# Reflow_Panel_Rev_D.net
KiCad netlist of a schematic drawn in EAGLE
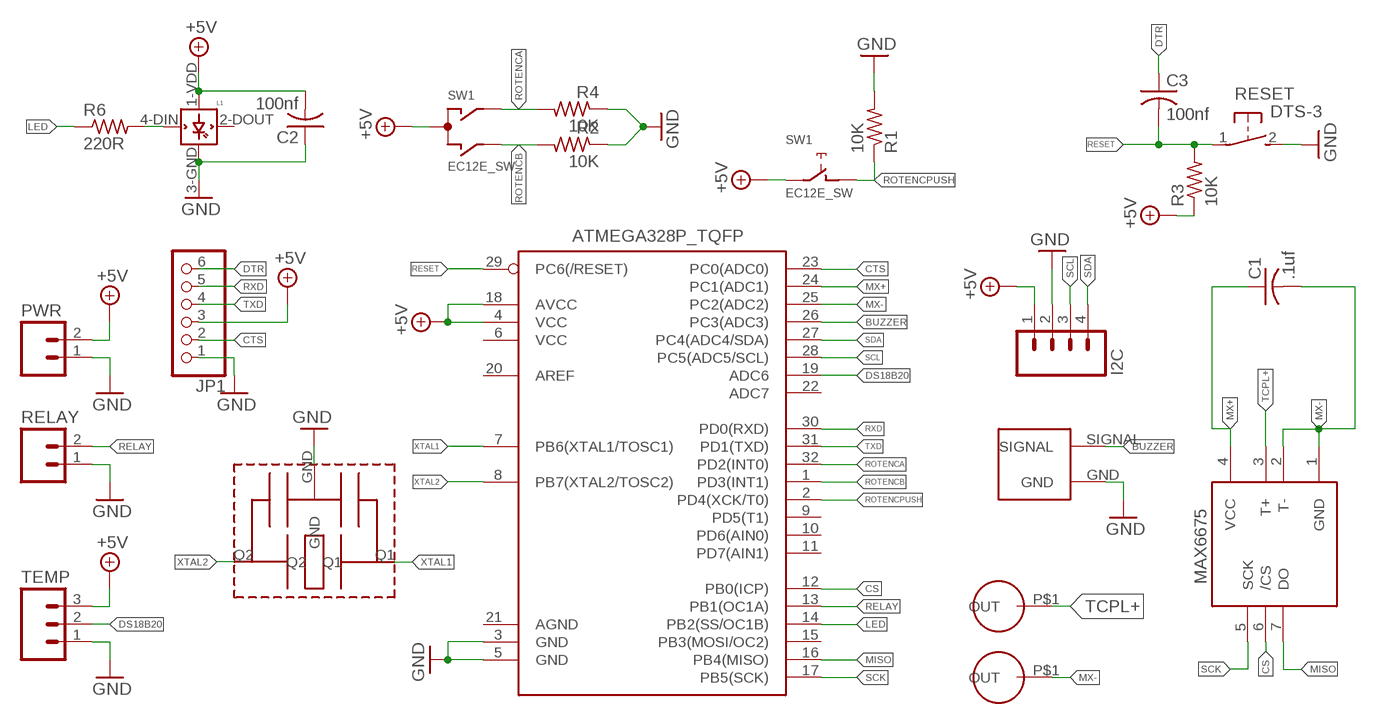
[diagram p0: schematic, sheet 1]

(export (version "E")
  (design (tool "Eeschema 10.0.6"))
  (components
    (comp (ref "C1")
      (value ".1uf")
      (footprint "eagle-import:C0805")
      (libsource (lib "eagle-import") (part "C-USC0805"))
    )
    (comp (ref "C2")
      (value "100nf")
      (footprint "eagle-import:C0805")
      (libsource (lib "eagle-import") (part "C-USC0805"))
    )
    (comp (ref "C3")
      (value "100nf")
      (footprint "eagle-import:C0805")
      (libsource (lib "eagle-import") (part "C-USC0805"))
    )
    (comp (ref "I2C")
      (value "M04LOCK_LONGPADS")
      (footprint "eagle-import:1X04_LOCK_LONGPADS")
      (libsource (lib "eagle-import") (part "M04LOCK_LONGPADS"))
    )
    (comp (ref "IC2")
      (value "MAX6675")
      (footprint "eagle-import:SO08")
      (libsource (lib "eagle-import") (part "MAX6675"))
    )
    (comp (ref "JP1")
      (value "PINHD-1X6LOCK")
      (footprint "eagle-import:1X06-BIGLOCK")
      (libsource (lib "eagle-import") (part "PINHD-1X6LOCK"))
    )
    (comp (ref "L1")
      (value "WS2812B_")
      (footprint "eagle-import:WS2812B")
      (libsource (lib "eagle-import") (part "WS2812B_"))
    )
    (comp (ref "PWR")
      (value "M02LOCK")
      (footprint "eagle-import:1X02_LOCK")
      (libsource (lib "eagle-import") (part "M02LOCK"))
    )
    (comp (ref "R1")
      (value "10K")
      (footprint "eagle-import:M0805")
      (libsource (lib "eagle-import") (part "R-US_M0805"))
    )
    (comp (ref "R2")
      (value "10K")
      (footprint "eagle-import:M0805")
      (libsource (lib "eagle-import") (part "R-US_M0805"))
    )
    (comp (ref "R3")
      (value "10K")
      (footprint "eagle-import:M0805")
      (libsource (lib "eagle-import") (part "R-US_M0805"))
    )
    (comp (ref "R4")
      (value "10K")
      (footprint "eagle-import:M0805")
      (libsource (lib "eagle-import") (part "R-US_M0805"))
    )
    (comp (ref "R6")
      (value "220R")
      (footprint "eagle-import:M0805")
      (libsource (lib "eagle-import") (part "R-US_M0805"))
    )
    (comp (ref "RELAY")
      (value "M02LOCK")
      (footprint "eagle-import:1X02_LOCK")
      (libsource (lib "eagle-import") (part "M02LOCK"))
    )
    (comp (ref "RESET")
      (value "DTS-3")
      (footprint "eagle-import:DTS-3")
      (libsource (lib "eagle-import") (part "DTS-3"))
    )
    (comp (ref "SW1")
      (value "EC12E_SW")
      (footprint "eagle-import:ALPS_EC12E_SW")
      (fields (field (name "MPN") "EC12E2424407"))
      (libsource (lib "eagle-import") (part "EC12E_SW"))
    )
    (comp (ref "TEMP")
      (value "M03LOCK")
      (footprint "eagle-import:1X03_LOCK")
      (libsource (lib "eagle-import") (part "M03LOCK"))
    )
    (comp (ref "U$1")
      (value "8.5MMSQUAREBUZZER")
      (footprint "eagle-import:8.5MMSQUAREBUZZER")
      (libsource (lib "eagle-import") (part "8.5MMSQUAREBUZZER"))
    )
    (comp (ref "U$2")
      (value "CSTCE16M0V53-R0")
      (footprint "eagle-import:CSTCE_V13C")
      (libsource (lib "eagle-import") (part "CSTCE16M0V53-R0"))
    )
    (comp (ref "U$3")
      (value "BANANAFEMAIL-10.8-5.7")
      (footprint "eagle-import:BANANAFEMALE-10.8-5.7")
      (libsource (lib "eagle-import") (part "BANANAFEMAIL-10.8-5.7"))
    )
    (comp (ref "U$4")
      (value "BANANAFEMAIL-10.8-5.7")
      (footprint "eagle-import:BANANAFEMALE-10.8-5.7")
      (libsource (lib "eagle-import") (part "BANANAFEMAIL-10.8-5.7"))
    )
    (comp (ref "U1")
      (value "ATMEGA328P_TQFP")
      (footprint "eagle-import:TQFP32-08")
      (libsource (lib "eagle-import") (part "ATMEGA328P_TQFP"))
    )
  )
  (nets
    (net (code "1") (name "+5V") (class "Default")
      (node (ref "C2") (pin "2") (pinfunction "2_2") (pintype "passive"))
      (node (ref "I2C") (pin "1") (pinfunction "1_1") (pintype "passive"))
      (node (ref "JP1") (pin "3") (pinfunction "3_3") (pintype "passive"))
      (node (ref "L1") (pin "1-VDD") (pinfunction "VDD_1-VDD") (pintype "bidirectional"))
      (node (ref "PWR") (pin "2") (pinfunction "2_2") (pintype "passive"))
      (node (ref "R3") (pin "1") (pinfunction "1_1") (pintype "passive"))
      (node (ref "SW1") (pin "C") (pinfunction "C_C") (pintype "passive"))
      (node (ref "SW1") (pin "E") (pinfunction "2_E") (pintype "passive"))
      (node (ref "TEMP") (pin "3") (pinfunction "3_3") (pintype "passive"))
      (node (ref "U1") (pin "18") (pinfunction "AVCC_18") (pintype "bidirectional"))
      (node (ref "U1") (pin "4") (pinfunction "VCC_4") (pintype "bidirectional"))
    )
    (net (code "2") (name "BUZZER") (class "Default")
      (node (ref "U$1") (pin "SIGNAL") (pinfunction "SIGNAL_SIGNAL") (pintype "bidirectional"))
      (node (ref "U1") (pin "26") (pinfunction "PC3(ADC3)_26") (pintype "bidirectional"))
    )
    (net (code "3") (name "CS") (class "Default")
      (node (ref "IC2") (pin "6") (pinfunction "/CS_6") (pintype "input"))
      (node (ref "U1") (pin "12") (pinfunction "PB0(ICP)_12") (pintype "bidirectional"))
    )
    (net (code "4") (name "CTS") (class "Default")
      (node (ref "JP1") (pin "2") (pinfunction "2_2") (pintype "passive"))
      (node (ref "U1") (pin "23") (pinfunction "PC0(ADC0)_23") (pintype "bidirectional"))
    )
    (net (code "5") (name "DS18B20") (class "Default")
      (node (ref "TEMP") (pin "2") (pinfunction "2_2") (pintype "passive"))
      (node (ref "U1") (pin "19") (pinfunction "ADC6_19") (pintype "bidirectional"))
    )
    (net (code "6") (name "DTR") (class "Default")
      (node (ref "C3") (pin "1") (pinfunction "1_1") (pintype "passive"))
      (node (ref "JP1") (pin "6") (pinfunction "6_6") (pintype "passive"))
    )
    (net (code "7") (name "GND") (class "Default")
      (node (ref "C2") (pin "1") (pinfunction "1_1") (pintype "passive"))
      (node (ref "I2C") (pin "2") (pinfunction "2_2") (pintype "passive"))
      (node (ref "JP1") (pin "1") (pinfunction "1_1") (pintype "passive"))
      (node (ref "L1") (pin "3-GND") (pinfunction "GND_3-GND") (pintype "bidirectional"))
      (node (ref "PWR") (pin "1") (pinfunction "1_1") (pintype "passive"))
      (node (ref "R1") (pin "2") (pinfunction "2_2") (pintype "passive"))
      (node (ref "R2") (pin "1") (pinfunction "1_1") (pintype "passive"))
      (node (ref "R4") (pin "1") (pinfunction "1_1") (pintype "passive"))
      (node (ref "RELAY") (pin "1") (pinfunction "1_1") (pintype "passive"))
      (node (ref "RESET") (pin "2") (pinfunction "2_2") (pintype "passive"))
      (node (ref "TEMP") (pin "1") (pinfunction "1_1") (pintype "passive"))
      (node (ref "U$1") (pin "GND") (pinfunction "GND_GND") (pintype "bidirectional"))
      (node (ref "U$2") (pin "GND") (pinfunction "GND_GND") (pintype "bidirectional"))
      (node (ref "U1") (pin "3") (pinfunction "GND_3") (pintype "bidirectional"))
      (node (ref "U1") (pin "5") (pinfunction "GND_5") (pintype "bidirectional"))
    )
    (net (code "8") (name "LED") (class "Default")
      (node (ref "R6") (pin "1") (pinfunction "1_1") (pintype "passive"))
      (node (ref "U1") (pin "14") (pinfunction "PB2(SS/OC1B)_14") (pintype "bidirectional"))
    )
    (net (code "9") (name "MISO") (class "Default")
      (node (ref "IC2") (pin "7") (pinfunction "DO_7") (pintype "output"))
      (node (ref "U1") (pin "16") (pinfunction "PB4(MISO)_16") (pintype "bidirectional"))
    )
    (net (code "10") (name "MX+") (class "Default")
      (node (ref "C1") (pin "1") (pinfunction "1_1") (pintype "passive"))
      (node (ref "IC2") (pin "4") (pinfunction "VCC_4") (pintype "power_in"))
      (node (ref "U1") (pin "24") (pinfunction "PC1(ADC1)_24") (pintype "bidirectional"))
    )
    (net (code "11") (name "MX-") (class "Default")
      (node (ref "C1") (pin "2") (pinfunction "2_2") (pintype "passive"))
      (node (ref "IC2") (pin "1") (pinfunction "GND_1") (pintype "power_in"))
      (node (ref "IC2") (pin "2") (pinfunction "T-_2") (pintype "input"))
      (node (ref "U$3") (pin "P$1") (pinfunction "OUT_P$1") (pintype "bidirectional"))
      (node (ref "U1") (pin "25") (pinfunction "PC2(ADC2)_25") (pintype "bidirectional"))
    )
    (net (code "12") (name "Net-(L1-DIN)") (class "Default")
      (node (ref "L1") (pin "4-DIN") (pinfunction "DIN_4-DIN") (pintype "input"))
      (node (ref "R6") (pin "2") (pinfunction "2_2") (pintype "passive"))
    )
    (net (code "13") (name "RELAY") (class "Default")
      (node (ref "RELAY") (pin "2") (pinfunction "2_2") (pintype "passive"))
      (node (ref "U1") (pin "13") (pinfunction "PB1(OC1A)_13") (pintype "bidirectional"))
    )
    (net (code "14") (name "RESET") (class "Default")
      (node (ref "C3") (pin "2") (pinfunction "2_2") (pintype "passive"))
      (node (ref "R3") (pin "2") (pinfunction "2_2") (pintype "passive"))
      (node (ref "RESET") (pin "1") (pinfunction "1_1") (pintype "passive"))
      (node (ref "U1") (pin "29") (pinfunction "PC6(/RESET)_29") (pintype "bidirectional"))
    )
    (net (code "15") (name "ROTENCA") (class "Default")
      (node (ref "R4") (pin "2") (pinfunction "2_2") (pintype "passive"))
      (node (ref "SW1") (pin "A") (pinfunction "A_A") (pintype "passive"))
      (node (ref "U1") (pin "32") (pinfunction "PD2(INT0)_32") (pintype "bidirectional"))
    )
    (net (code "16") (name "ROTENCB") (class "Default")
      (node (ref "R2") (pin "2") (pinfunction "2_2") (pintype "passive"))
      (node (ref "SW1") (pin "B") (pinfunction "B_B") (pintype "passive"))
      (node (ref "U1") (pin "1") (pinfunction "PD3(INT1)_1") (pintype "bidirectional"))
    )
    (net (code "17") (name "ROTENCPUSH") (class "Default")
      (node (ref "R1") (pin "1") (pinfunction "1_1") (pintype "passive"))
      (node (ref "SW1") (pin "D") (pinfunction "1_D") (pintype "passive"))
      (node (ref "U1") (pin "2") (pinfunction "PD4(XCK/T0)_2") (pintype "bidirectional"))
    )
    (net (code "18") (name "RXD") (class "Default")
      (node (ref "JP1") (pin "5") (pinfunction "5_5") (pintype "passive"))
      (node (ref "U1") (pin "30") (pinfunction "PD0(RXD)_30") (pintype "bidirectional"))
    )
    (net (code "19") (name "SCK") (class "Default")
      (node (ref "IC2") (pin "5") (pinfunction "SCK_5") (pintype "input"))
      (node (ref "U1") (pin "17") (pinfunction "PB5(SCK)_17") (pintype "bidirectional"))
    )
    (net (code "20") (name "SCL") (class "Default")
      (node (ref "I2C") (pin "3") (pinfunction "3_3") (pintype "passive"))
      (node (ref "U1") (pin "28") (pinfunction "PC5(ADC5/SCL)_28") (pintype "bidirectional"))
    )
    (net (code "21") (name "SDA") (class "Default")
      (node (ref "I2C") (pin "4") (pinfunction "4_4") (pintype "passive"))
      (node (ref "U1") (pin "27") (pinfunction "PC4(ADC4/SDA)_27") (pintype "bidirectional"))
    )
    (net (code "22") (name "TCPL+") (class "Default")
      (node (ref "IC2") (pin "3") (pinfunction "T+_3") (pintype "input"))
      (node (ref "U$4") (pin "P$1") (pinfunction "OUT_P$1") (pintype "bidirectional"))
    )
    (net (code "23") (name "TXD") (class "Default")
      (node (ref "JP1") (pin "4") (pinfunction "4_4") (pintype "passive"))
      (node (ref "U1") (pin "31") (pinfunction "PD1(TXD)_31") (pintype "bidirectional"))
    )
    (net (code "24") (name "XTAL1") (class "Default")
      (node (ref "U$2") (pin "Q1") (pinfunction "Q1_Q1") (pintype "bidirectional"))
      (node (ref "U1") (pin "7") (pinfunction "PB6(XTAL1/TOSC1)_7") (pintype "bidirectional"))
    )
    (net (code "25") (name "XTAL2") (class "Default")
      (node (ref "U$2") (pin "Q2") (pinfunction "Q2_Q2") (pintype "bidirectional"))
      (node (ref "U1") (pin "8") (pinfunction "PB7(XTAL2/TOSC2)_8") (pintype "bidirectional"))
    )
    (net (code "26") (name "unconnected-(L1-DOUT-Pad2-DOUT)") (class "Default")
      (node (ref "L1") (pin "2-DOUT") (pinfunction "DOUT_2-DOUT") (pintype "output"))
    )
    (net (code "27") (name "unconnected-(U1-ADC7-Pad22)") (class "Default")
      (node (ref "U1") (pin "22") (pinfunction "ADC7_22") (pintype "bidirectional"))
    )
    (net (code "28") (name "unconnected-(U1-AGND-Pad21)") (class "Default")
      (node (ref "U1") (pin "21") (pinfunction "AGND_21") (pintype "bidirectional"))
    )
    (net (code "29") (name "unconnected-(U1-AREF-Pad20)") (class "Default")
      (node (ref "U1") (pin "20") (pinfunction "AREF_20") (pintype "bidirectional"))
    )
    (net (code "30") (name "unconnected-(U1-PB3(MOSI{slash}OC2)-Pad15)") (class "Default")
      (node (ref "U1") (pin "15") (pinfunction "PB3(MOSI/OC2)_15") (pintype "bidirectional"))
    )
    (net (code "31") (name "unconnected-(U1-PD5(T1)-Pad9)") (class "Default")
      (node (ref "U1") (pin "9") (pinfunction "PD5(T1)_9") (pintype "bidirectional"))
    )
    (net (code "32") (name "unconnected-(U1-PD6(AIN0)-Pad10)") (class "Default")
      (node (ref "U1") (pin "10") (pinfunction "PD6(AIN0)_10") (pintype "bidirectional"))
    )
    (net (code "33") (name "unconnected-(U1-PD7(AIN1)-Pad11)") (class "Default")
      (node (ref "U1") (pin "11") (pinfunction "PD7(AIN1)_11") (pintype "bidirectional"))
    )
    (net (code "34") (name "unconnected-(U1-VCC-Pad6)") (class "Default")
      (node (ref "U1") (pin "6") (pinfunction "VCC_6") (pintype "bidirectional"))
    )
  )
)
